# question_3.net
KiCad netlist of a schematic drawn in EAGLE
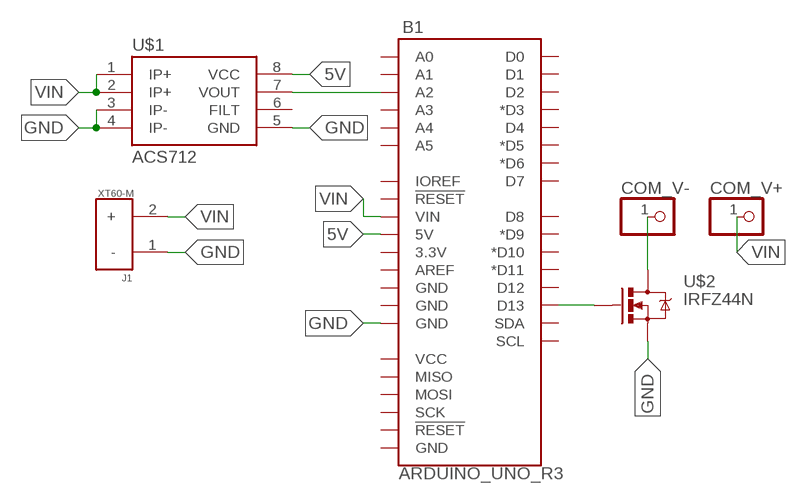
[diagram p0: schematic, sheet 1]

(export (version "E")
  (design (tool "Eeschema 10.0.6"))
  (components
    (comp (ref "B1")
      (value "ARDUINO_UNO_R3")
      (footprint "eagle-import:ARDUINO_R3")
      (libsource (lib "eagle-import") (part "ARDUINO_UNO_R3"))
    )
    (comp (ref "COM_V+")
      (value "PINHD-1X1")
      (footprint "eagle-import:1X01")
      (libsource (lib "eagle-import") (part "PINHD-1X1"))
    )
    (comp (ref "COM_V-")
      (value "PINHD-1X1")
      (footprint "eagle-import:1X01")
      (libsource (lib "eagle-import") (part "PINHD-1X1"))
    )
    (comp (ref "J1")
      (value "XT60-M")
      (footprint "eagle-import:AMASS_XT60-M")
      (fields (field (name "MF") "AMASS"))
      (libsource (lib "eagle-import") (part "XT60-M"))
    )
    (comp (ref "U$1")
      (value "ACS712")
      (footprint "eagle-import:SO08")
      (libsource (lib "eagle-import") (part "ACS712"))
    )
    (comp (ref "U$2")
      (value "IRFZ44N")
      (footprint "eagle-import:TO-220")
      (fields (field (name "MF") "Infineon Technologies"))
      (libsource (lib "eagle-import") (part "IRFZ44N"))
    )
  )
  (nets
    (net (code "1") (name "5V") (class "Default")
      (node (ref "B1") (pin "5V") (pinfunction "5V_5V") (pintype "bidirectional"))
      (node (ref "U$1") (pin "8") (pinfunction "VCC_8") (pintype "bidirectional"))
    )
    (net (code "2") (name "GND") (class "Default")
      (node (ref "B1") (pin "GND@2") (pinfunction "GND_GND@2") (pintype "bidirectional"))
      (node (ref "J1") (pin "1") (pinfunction "-_1") (pintype "passive"))
      (node (ref "U$1") (pin "3") (pinfunction "IP-_3") (pintype "bidirectional"))
      (node (ref "U$1") (pin "4") (pinfunction "IP-_4") (pintype "bidirectional"))
      (node (ref "U$1") (pin "5") (pinfunction "GND_5") (pintype "bidirectional"))
      (node (ref "U$2") (pin "3") (pinfunction "S_3") (pintype "passive"))
    )
    (net (code "3") (name "Net-(U$1-VOUT)") (class "Default")
      (node (ref "B1") (pin "A2") (pinfunction "A2_A2") (pintype "bidirectional"))
      (node (ref "U$1") (pin "7") (pinfunction "VOUT_7") (pintype "bidirectional"))
    )
    (net (code "4") (name "Net-(U$2-D)") (class "Default")
      (node (ref "COM_V-") (pin "1") (pinfunction "1_1") (pintype "passive"))
      (node (ref "U$2") (pin "2") (pinfunction "D_2") (pintype "passive"))
    )
    (net (code "5") (name "Net-(U$2-G)") (class "Default")
      (node (ref "B1") (pin "D13") (pinfunction "D13_D13") (pintype "bidirectional"))
      (node (ref "U$2") (pin "1") (pinfunction "G_1") (pintype "passive"))
    )
    (net (code "6") (name "VIN") (class "Default")
      (node (ref "B1") (pin "VIN") (pinfunction "VIN_VIN") (pintype "bidirectional"))
      (node (ref "COM_V+") (pin "1") (pinfunction "1_1") (pintype "passive"))
      (node (ref "J1") (pin "2") (pinfunction "+_2") (pintype "passive"))
      (node (ref "U$1") (pin "1") (pinfunction "IP+_1") (pintype "bidirectional"))
      (node (ref "U$1") (pin "2") (pinfunction "IP+_2") (pintype "bidirectional"))
    )
    (net (code "7") (name "unconnected-(B1-*D3-PadD3)") (class "Default")
      (node (ref "B1") (pin "D3") (pinfunction "*D3_D3") (pintype "bidirectional"))
    )
    (net (code "8") (name "unconnected-(B1-*D5-PadD5)") (class "Default")
      (node (ref "B1") (pin "D5") (pinfunction "*D5_D5") (pintype "bidirectional"))
    )
    (net (code "9") (name "unconnected-(B1-*D6-PadD6)") (class "Default")
      (node (ref "B1") (pin "D6") (pinfunction "*D6_D6") (pintype "bidirectional"))
    )
    (net (code "10") (name "unconnected-(B1-*D9-PadD9)") (class "Default")
      (node (ref "B1") (pin "D9") (pinfunction "*D9_D9") (pintype "bidirectional"))
    )
    (net (code "11") (name "unconnected-(B1-*D10-PadD10)") (class "Default")
      (node (ref "B1") (pin "D10") (pinfunction "*D10_D10") (pintype "bidirectional"))
    )
    (net (code "12") (name "unconnected-(B1-*D11-PadD11)") (class "Default")
      (node (ref "B1") (pin "D11") (pinfunction "*D11_D11") (pintype "bidirectional"))
    )
    (net (code "13") (name "unconnected-(B1-GND-PadGND@1)") (class "Default")
      (node (ref "B1") (pin "GND@1") (pinfunction "GND_GND@1") (pintype "bidirectional"))
    )
    (net (code "14") (name "unconnected-(B1-GND-PadGND@3)") (class "Default")
      (node (ref "B1") (pin "GND@3") (pinfunction "GND_GND@3") (pintype "bidirectional"))
    )
    (net (code "15") (name "unconnected-(B1-GND-PadGND@4)") (class "Default")
      (node (ref "B1") (pin "GND@4") (pinfunction "GND_GND@4") (pintype "bidirectional"))
    )
    (net (code "16") (name "unconnected-(B1-Pad3.3V)") (class "Default")
      (node (ref "B1") (pin "3.3V") (pinfunction "3.3V_3.3V") (pintype "bidirectional"))
    )
    (net (code "17") (name "unconnected-(B1-PadA0)") (class "Default")
      (node (ref "B1") (pin "A0") (pinfunction "A0_A0") (pintype "bidirectional"))
    )
    (net (code "18") (name "unconnected-(B1-PadA1)") (class "Default")
      (node (ref "B1") (pin "A1") (pinfunction "A1_A1") (pintype "bidirectional"))
    )
    (net (code "19") (name "unconnected-(B1-PadA3)") (class "Default")
      (node (ref "B1") (pin "A3") (pinfunction "A3_A3") (pintype "bidirectional"))
    )
    (net (code "20") (name "unconnected-(B1-PadA4)") (class "Default")
      (node (ref "B1") (pin "A4") (pinfunction "A4_A4") (pintype "bidirectional"))
    )
    (net (code "21") (name "unconnected-(B1-PadA5)") (class "Default")
      (node (ref "B1") (pin "A5") (pinfunction "A5_A5") (pintype "bidirectional"))
    )
    (net (code "22") (name "unconnected-(B1-PadAREF)") (class "Default")
      (node (ref "B1") (pin "AREF") (pinfunction "AREF_AREF") (pintype "bidirectional"))
    )
    (net (code "23") (name "unconnected-(B1-PadD0)") (class "Default")
      (node (ref "B1") (pin "D0") (pinfunction "D0_D0") (pintype "bidirectional"))
    )
    (net (code "24") (name "unconnected-(B1-PadD1)") (class "Default")
      (node (ref "B1") (pin "D1") (pinfunction "D1_D1") (pintype "bidirectional"))
    )
    (net (code "25") (name "unconnected-(B1-PadD2)") (class "Default")
      (node (ref "B1") (pin "D2") (pinfunction "D2_D2") (pintype "bidirectional"))
    )
    (net (code "26") (name "unconnected-(B1-PadD4)") (class "Default")
      (node (ref "B1") (pin "D4") (pinfunction "D4_D4") (pintype "bidirectional"))
    )
    (net (code "27") (name "unconnected-(B1-PadD7)") (class "Default")
      (node (ref "B1") (pin "D7") (pinfunction "D7_D7") (pintype "bidirectional"))
    )
    (net (code "28") (name "unconnected-(B1-PadD8)") (class "Default")
      (node (ref "B1") (pin "D8") (pinfunction "D8_D8") (pintype "bidirectional"))
    )
    (net (code "29") (name "unconnected-(B1-PadD12)") (class "Default")
      (node (ref "B1") (pin "D12") (pinfunction "D12_D12") (pintype "bidirectional"))
    )
    (net (code "30") (name "unconnected-(B1-PadIOREF)") (class "Default")
      (node (ref "B1") (pin "IOREF") (pinfunction "IOREF_IOREF") (pintype "bidirectional"))
    )
    (net (code "31") (name "unconnected-(B1-PadMISO)") (class "Default")
      (node (ref "B1") (pin "MISO") (pinfunction "MISO_MISO") (pintype "bidirectional"))
    )
    (net (code "32") (name "unconnected-(B1-PadMOSI)") (class "Default")
      (node (ref "B1") (pin "MOSI") (pinfunction "MOSI_MOSI") (pintype "bidirectional"))
    )
    (net (code "33") (name "unconnected-(B1-PadSCK)") (class "Default")
      (node (ref "B1") (pin "SCK") (pinfunction "SCK_SCK") (pintype "bidirectional"))
    )
    (net (code "34") (name "unconnected-(B1-PadSCL)") (class "Default")
      (node (ref "B1") (pin "SCL") (pinfunction "SCL_SCL") (pintype "bidirectional"))
    )
    (net (code "35") (name "unconnected-(B1-PadSDA)") (class "Default")
      (node (ref "B1") (pin "SDA") (pinfunction "SDA_SDA") (pintype "bidirectional"))
    )
    (net (code "36") (name "unconnected-(B1-PadVCC)") (class "Default")
      (node (ref "B1") (pin "VCC") (pinfunction "VCC_VCC") (pintype "bidirectional"))
    )
    (net (code "37") (name "unconnected-(B1-~{RESET}-PadRESET@1)") (class "Default")
      (node (ref "B1") (pin "RESET@1") (pinfunction "~{RESET}_RESET@1") (pintype "bidirectional"))
    )
    (net (code "38") (name "unconnected-(B1-~{RESET}-PadRESET@2)") (class "Default")
      (node (ref "B1") (pin "RESET@2") (pinfunction "~{RESET}_RESET@2") (pintype "bidirectional"))
    )
    (net (code "39") (name "unconnected-(U$1-FILT-Pad6)") (class "Default")
      (node (ref "U$1") (pin "6") (pinfunction "FILT_6") (pintype "bidirectional"))
    )
  )
)
